# Sheet1.net
KiCad netlist of a schematic drawn in Altium Designer
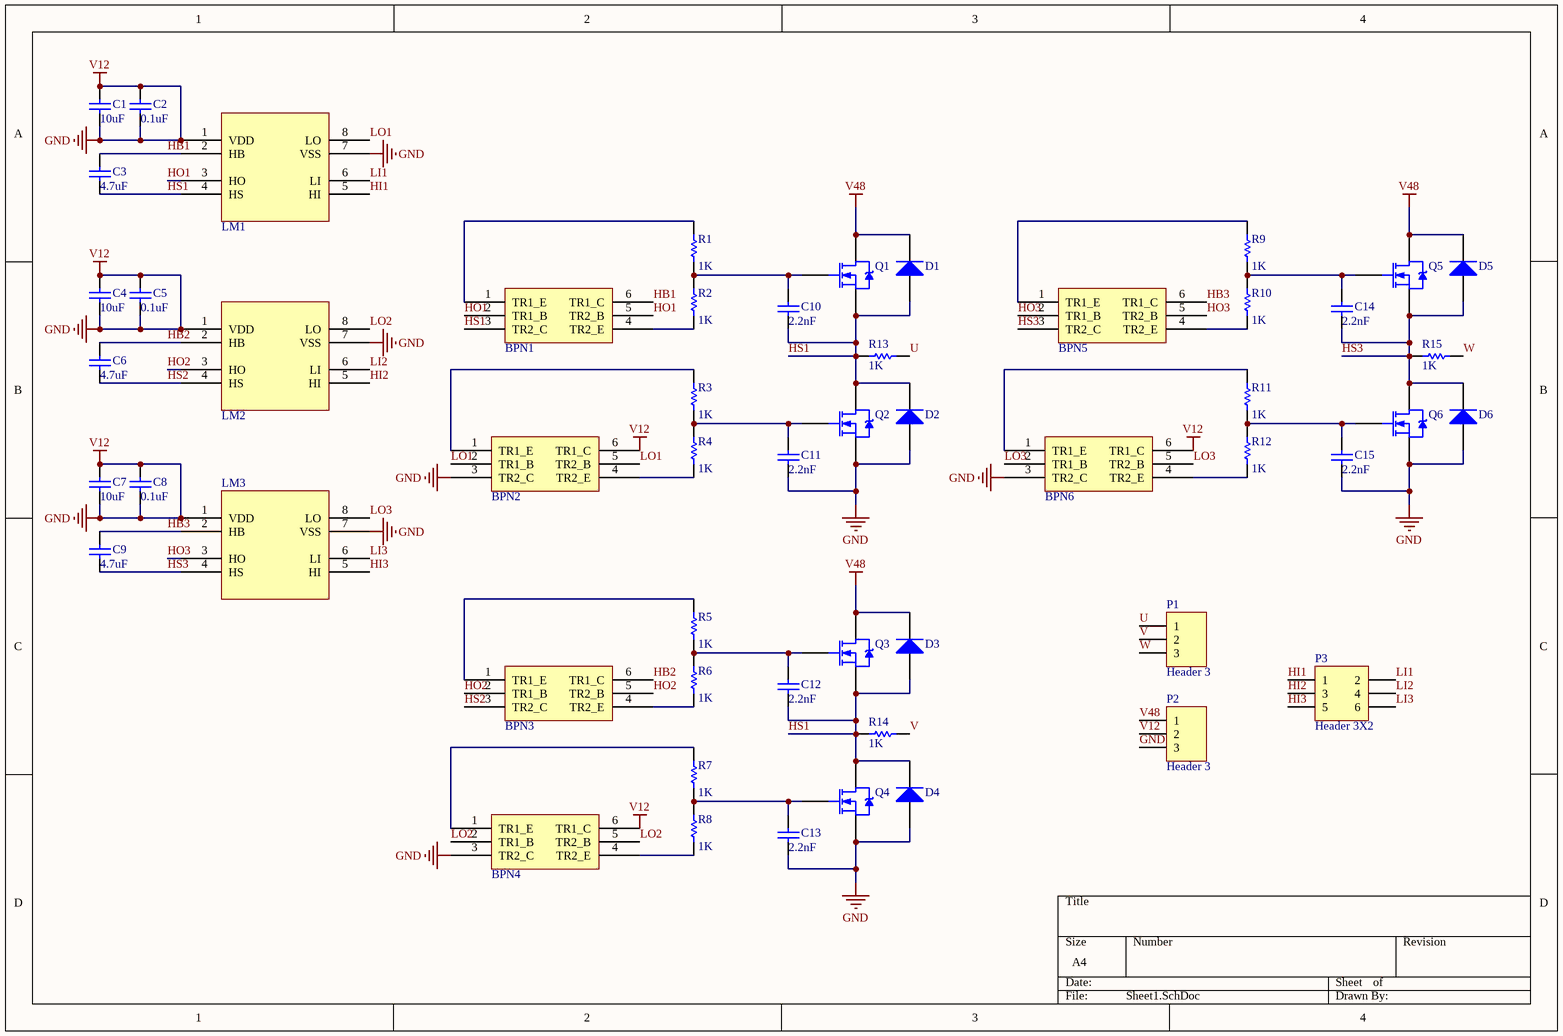
[diagram p0: Sheet1.SchDoc]

(export (version "E")
  (design (tool "Eeschema 10.0.6"))
  (components
    (comp (ref "BPN1") (value "BPN1") (footprint "BC847BPN") (libsource (lib "BC847BPN") (part "BC847BPN")))
    (comp (ref "BPN2") (value "BPN2") (footprint "BC847BPN") (libsource (lib "BC847BPN") (part "BC847BPN")))
    (comp (ref "BPN3") (value "BPN3") (footprint "BC847BPN") (libsource (lib "BC847BPN") (part "BC847BPN")))
    (comp (ref "BPN4") (value "BPN4") (footprint "BC847BPN") (libsource (lib "BC847BPN") (part "BC847BPN")))
    (comp (ref "BPN5") (value "BPN5") (footprint "BC847BPN") (libsource (lib "BC847BPN") (part "BC847BPN")))
    (comp (ref "BPN6") (value "BPN6") (footprint "BC847BPN") (libsource (lib "BC847BPN") (part "BC847BPN")))
    (comp (ref "C1")
      (value "10uF")
      (footprint "6-0805_M")
      (description "Capacitor")
      (fields (field (name "Comment") "Cap") (field (name "PUBLISHER") "Altium Limited"))
      (libsource (lib "Miscellaneous Devices") (part "Cap"))
    )
    (comp (ref "C2")
      (value "0.1uF")
      (footprint "6-0805_M")
      (description "Capacitor")
      (fields (field (name "Comment") "Cap") (field (name "PUBLISHER") "Altium Limited"))
      (libsource (lib "Miscellaneous Devices") (part "Cap"))
    )
    (comp (ref "C3")
      (value "4.7uF")
      (footprint "6-0805_M")
      (description "Capacitor")
      (fields (field (name "Comment") "Cap") (field (name "PUBLISHER") "Altium Limited"))
      (libsource (lib "Miscellaneous Devices") (part "Cap"))
    )
    (comp (ref "C4")
      (value "10uF")
      (footprint "6-0805_M")
      (description "Capacitor")
      (fields (field (name "Comment") "Cap") (field (name "PUBLISHER") "Altium Limited"))
      (libsource (lib "Miscellaneous Devices") (part "Cap"))
    )
    (comp (ref "C5")
      (value "0.1uF")
      (footprint "6-0805_M")
      (description "Capacitor")
      (fields (field (name "Comment") "Cap") (field (name "PUBLISHER") "Altium Limited"))
      (libsource (lib "Miscellaneous Devices") (part "Cap"))
    )
    (comp (ref "C6")
      (value "4.7uF")
      (footprint "6-0805_M")
      (description "Capacitor")
      (fields (field (name "Comment") "Cap") (field (name "PUBLISHER") "Altium Limited"))
      (libsource (lib "Miscellaneous Devices") (part "Cap"))
    )
    (comp (ref "C7")
      (value "10uF")
      (footprint "6-0805_M")
      (description "Capacitor")
      (fields (field (name "Comment") "Cap") (field (name "PUBLISHER") "Altium Limited"))
      (libsource (lib "Miscellaneous Devices") (part "Cap"))
    )
    (comp (ref "C8")
      (value "0.1uF")
      (footprint "6-0805_M")
      (description "Capacitor")
      (fields (field (name "Comment") "Cap") (field (name "PUBLISHER") "Altium Limited"))
      (libsource (lib "Miscellaneous Devices") (part "Cap"))
    )
    (comp (ref "C9")
      (value "4.7uF")
      (footprint "6-0805_M")
      (description "Capacitor")
      (fields (field (name "Comment") "Cap") (field (name "PUBLISHER") "Altium Limited"))
      (libsource (lib "Miscellaneous Devices") (part "Cap"))
    )
    (comp (ref "C10")
      (value "2.2nF")
      (footprint "6-0805_M")
      (description "Capacitor")
      (fields (field (name "Comment") "Cap") (field (name "PUBLISHER") "Altium Limited"))
      (libsource (lib "Miscellaneous Devices") (part "Cap"))
    )
    (comp (ref "C11")
      (value "2.2nF")
      (footprint "6-0805_M")
      (description "Capacitor")
      (fields (field (name "Comment") "Cap") (field (name "PUBLISHER") "Altium Limited"))
      (libsource (lib "Miscellaneous Devices") (part "Cap"))
    )
    (comp (ref "C12")
      (value "2.2nF")
      (footprint "6-0805_M")
      (description "Capacitor")
      (fields (field (name "Comment") "Cap") (field (name "PUBLISHER") "Altium Limited"))
      (libsource (lib "Miscellaneous Devices") (part "Cap"))
    )
    (comp (ref "C13")
      (value "2.2nF")
      (footprint "6-0805_M")
      (description "Capacitor")
      (fields (field (name "Comment") "Cap") (field (name "PUBLISHER") "Altium Limited"))
      (libsource (lib "Miscellaneous Devices") (part "Cap"))
    )
    (comp (ref "C14")
      (value "2.2nF")
      (footprint "6-0805_M")
      (description "Capacitor")
      (fields (field (name "Comment") "Cap") (field (name "PUBLISHER") "Altium Limited"))
      (libsource (lib "Miscellaneous Devices") (part "Cap"))
    )
    (comp (ref "C15")
      (value "2.2nF")
      (footprint "6-0805_M")
      (description "Capacitor")
      (fields (field (name "Comment") "Cap") (field (name "PUBLISHER") "Altium Limited"))
      (libsource (lib "Miscellaneous Devices") (part "Cap"))
    )
    (comp (ref "D1")
      (value "Diode 1N914")
      (footprint "12Z-2010")
      (description "High Conductance Fast Diode")
      (fields (field (name "PUBLISHER") "Altium Limited"))
      (libsource (lib "Miscellaneous Devices") (part "Diode 1N914"))
    )
    (comp (ref "D2")
      (value "Diode 1N914")
      (footprint "12Z-2010")
      (description "High Conductance Fast Diode")
      (fields (field (name "PUBLISHER") "Altium Limited"))
      (libsource (lib "Miscellaneous Devices") (part "Diode 1N914"))
    )
    (comp (ref "D3")
      (value "Diode 1N914")
      (footprint "12Z-2010")
      (description "High Conductance Fast Diode")
      (fields (field (name "PUBLISHER") "Altium Limited"))
      (libsource (lib "Miscellaneous Devices") (part "Diode 1N914"))
    )
    (comp (ref "D4")
      (value "Diode 1N914")
      (footprint "12Z-2010")
      (description "High Conductance Fast Diode")
      (fields (field (name "PUBLISHER") "Altium Limited"))
      (libsource (lib "Miscellaneous Devices") (part "Diode 1N914"))
    )
    (comp (ref "D5")
      (value "Diode 1N914")
      (footprint "12Z-2010")
      (description "High Conductance Fast Diode")
      (fields (field (name "PUBLISHER") "Altium Limited"))
      (libsource (lib "Miscellaneous Devices") (part "Diode 1N914"))
    )
    (comp (ref "D6")
      (value "Diode 1N914")
      (footprint "12Z-2010")
      (description "High Conductance Fast Diode")
      (fields (field (name "PUBLISHER") "Altium Limited"))
      (libsource (lib "Miscellaneous Devices") (part "Diode 1N914"))
    )
    (comp (ref "LM1") (value "LM1") (footprint "LM5101A") (libsource (lib "LM5101A") (part "LM5101A")))
    (comp (ref "LM2") (value "LM2") (footprint "LM5101A") (libsource (lib "LM5101A") (part "LM5101A")))
    (comp (ref "LM3") (value "LM3") (footprint "LM5101A") (libsource (lib "LM5101A") (part "LM5101A")))
    (comp (ref "P1")
      (value "Header 3")
      (footprint "HDR1X3")
      (description "Header, 3-Pin")
      (fields (field (name "PUBLISHER") "Altium Limited"))
      (libsource (lib "Miscellaneous Connectors") (part "Header 3"))
    )
    (comp (ref "P2")
      (value "Header 3")
      (footprint "HDR1X3")
      (description "Header, 3-Pin")
      (fields (field (name "PUBLISHER") "Altium Limited"))
      (libsource (lib "Miscellaneous Connectors") (part "Header 3"))
    )
    (comp (ref "P3")
      (value "Header 3X2")
      (footprint "HDR2X3")
      (description "Header, 3-Pin, Dual row")
      (fields (field (name "PUBLISHER") "Altium Limited"))
      (libsource (lib "Miscellaneous Connectors") (part "Header 3X2"))
    )
    (comp (ref "Q1")
      (value "NMOS-2")
      (footprint "SOT-23_M")
      (description "N-Channel Power MOSFET")
      (fields (field (name "PUBLISHER") "Altium Limited"))
      (libsource (lib "Miscellaneous Devices") (part "NMOS-2"))
    )
    (comp (ref "Q2")
      (value "NMOS-2")
      (footprint "SOT23_M")
      (description "N-Channel Power MOSFET")
      (fields (field (name "PUBLISHER") "Altium Limited"))
      (libsource (lib "Miscellaneous Devices") (part "NMOS-2"))
    )
    (comp (ref "Q3")
      (value "NMOS-2")
      (footprint "SOT-23_M")
      (description "N-Channel Power MOSFET")
      (fields (field (name "PUBLISHER") "Altium Limited"))
      (libsource (lib "Miscellaneous Devices") (part "NMOS-2"))
    )
    (comp (ref "Q4")
      (value "NMOS-2")
      (footprint "SOT23_M")
      (description "N-Channel Power MOSFET")
      (fields (field (name "PUBLISHER") "Altium Limited"))
      (libsource (lib "Miscellaneous Devices") (part "NMOS-2"))
    )
    (comp (ref "Q5")
      (value "NMOS-2")
      (footprint "SOT-23_M")
      (description "N-Channel Power MOSFET")
      (fields (field (name "PUBLISHER") "Altium Limited"))
      (libsource (lib "Miscellaneous Devices") (part "NMOS-2"))
    )
    (comp (ref "Q6")
      (value "NMOS-2")
      (footprint "SOT23_M")
      (description "N-Channel Power MOSFET")
      (fields (field (name "PUBLISHER") "Altium Limited"))
      (libsource (lib "Miscellaneous Devices") (part "NMOS-2"))
    )
    (comp (ref "R1")
      (value "1K")
      (footprint "6-0805_M")
      (description "Resistor")
      (fields (field (name "Comment") "Res1") (field (name "PUBLISHER") "Altium Limited"))
      (libsource (lib "Miscellaneous Devices") (part "Res1"))
    )
    (comp (ref "R2")
      (value "1K")
      (footprint "6-0805_M")
      (description "Resistor")
      (fields (field (name "Comment") "Res1") (field (name "PUBLISHER") "Altium Limited"))
      (libsource (lib "Miscellaneous Devices") (part "Res1"))
    )
    (comp (ref "R3")
      (value "1K")
      (footprint "6-0805_M")
      (description "Resistor")
      (fields (field (name "Comment") "Res1") (field (name "PUBLISHER") "Altium Limited"))
      (libsource (lib "Miscellaneous Devices") (part "Res1"))
    )
    (comp (ref "R4")
      (value "1K")
      (footprint "6-0805_M")
      (description "Resistor")
      (fields (field (name "Comment") "Res1") (field (name "PUBLISHER") "Altium Limited"))
      (libsource (lib "Miscellaneous Devices") (part "Res1"))
    )
    (comp (ref "R5")
      (value "1K")
      (footprint "6-0805_M")
      (description "Resistor")
      (fields (field (name "Comment") "Res1") (field (name "PUBLISHER") "Altium Limited"))
      (libsource (lib "Miscellaneous Devices") (part "Res1"))
    )
    (comp (ref "R6")
      (value "1K")
      (footprint "6-0805_M")
      (description "Resistor")
      (fields (field (name "Comment") "Res1") (field (name "PUBLISHER") "Altium Limited"))
      (libsource (lib "Miscellaneous Devices") (part "Res1"))
    )
    (comp (ref "R7")
      (value "1K")
      (footprint "6-0805_M")
      (description "Resistor")
      (fields (field (name "Comment") "Res1") (field (name "PUBLISHER") "Altium Limited"))
      (libsource (lib "Miscellaneous Devices") (part "Res1"))
    )
    (comp (ref "R8")
      (value "1K")
      (footprint "6-0805_M")
      (description "Resistor")
      (fields (field (name "Comment") "Res1") (field (name "PUBLISHER") "Altium Limited"))
      (libsource (lib "Miscellaneous Devices") (part "Res1"))
    )
    (comp (ref "R9")
      (value "1K")
      (footprint "6-0805_M")
      (description "Resistor")
      (fields (field (name "Comment") "Res1") (field (name "PUBLISHER") "Altium Limited"))
      (libsource (lib "Miscellaneous Devices") (part "Res1"))
    )
    (comp (ref "R10")
      (value "1K")
      (footprint "6-0805_M")
      (description "Resistor")
      (fields (field (name "Comment") "Res1") (field (name "PUBLISHER") "Altium Limited"))
      (libsource (lib "Miscellaneous Devices") (part "Res1"))
    )
    (comp (ref "R11")
      (value "1K")
      (footprint "6-0805_M")
      (description "Resistor")
      (fields (field (name "Comment") "Res1") (field (name "PUBLISHER") "Altium Limited"))
      (libsource (lib "Miscellaneous Devices") (part "Res1"))
    )
    (comp (ref "R12")
      (value "1K")
      (footprint "6-0805_M")
      (description "Resistor")
      (fields (field (name "Comment") "Res1") (field (name "PUBLISHER") "Altium Limited"))
      (libsource (lib "Miscellaneous Devices") (part "Res1"))
    )
    (comp (ref "R13")
      (value "1K")
      (footprint "6-0805_M")
      (description "Resistor")
      (fields (field (name "Comment") "Res1") (field (name "PUBLISHER") "Altium Limited"))
      (libsource (lib "Miscellaneous Devices") (part "Res1"))
    )
    (comp (ref "R14")
      (value "1K")
      (footprint "6-0805_M")
      (description "Resistor")
      (fields (field (name "Comment") "Res1") (field (name "PUBLISHER") "Altium Limited"))
      (libsource (lib "Miscellaneous Devices") (part "Res1"))
    )
    (comp (ref "R15")
      (value "1K")
      (footprint "6-0805_M")
      (description "Resistor")
      (fields (field (name "Comment") "Res1") (field (name "PUBLISHER") "Altium Limited"))
      (libsource (lib "Miscellaneous Devices") (part "Res1"))
    )
  )
  (nets
    (net (code "1") (name "/HB1") (class "Default")
      (node (ref "BPN1") (pin "6") (pinfunction "TR1_C_6") (pintype "passive"))
      (node (ref "C3") (pin "2") (pinfunction "2_2") (pintype "passive"))
      (node (ref "LM1") (pin "2") (pinfunction "HB_2") (pintype "passive"))
    )
    (net (code "2") (name "/HB2") (class "Default")
      (node (ref "BPN3") (pin "6") (pinfunction "TR1_C_6") (pintype "passive"))
      (node (ref "C6") (pin "2") (pinfunction "2_2") (pintype "passive"))
      (node (ref "LM2") (pin "2") (pinfunction "HB_2") (pintype "passive"))
    )
    (net (code "3") (name "/HB3") (class "Default")
      (node (ref "BPN5") (pin "6") (pinfunction "TR1_C_6") (pintype "passive"))
      (node (ref "C9") (pin "2") (pinfunction "2_2") (pintype "passive"))
      (node (ref "LM3") (pin "2") (pinfunction "HB_2") (pintype "passive"))
    )
    (net (code "4") (name "/HI1") (class "Default")
      (node (ref "LM1") (pin "5") (pinfunction "HI_5") (pintype "passive"))
      (node (ref "P3") (pin "1") (pinfunction "1_1") (pintype "passive"))
    )
    (net (code "5") (name "/HI2") (class "Default")
      (node (ref "LM2") (pin "5") (pinfunction "HI_5") (pintype "passive"))
      (node (ref "P3") (pin "3") (pinfunction "3_3") (pintype "passive"))
    )
    (net (code "6") (name "/HI3") (class "Default")
      (node (ref "LM3") (pin "5") (pinfunction "HI_5") (pintype "passive"))
      (node (ref "P3") (pin "5") (pinfunction "5_5") (pintype "passive"))
    )
    (net (code "7") (name "/HO1") (class "Default")
      (node (ref "BPN1") (pin "2") (pinfunction "TR1_B_2") (pintype "passive"))
      (node (ref "BPN1") (pin "5") (pinfunction "TR2_B_5") (pintype "passive"))
      (node (ref "LM1") (pin "3") (pinfunction "HO_3") (pintype "passive"))
    )
    (net (code "8") (name "/HO2") (class "Default")
      (node (ref "BPN3") (pin "2") (pinfunction "TR1_B_2") (pintype "passive"))
      (node (ref "BPN3") (pin "5") (pinfunction "TR2_B_5") (pintype "passive"))
      (node (ref "LM2") (pin "3") (pinfunction "HO_3") (pintype "passive"))
    )
    (net (code "9") (name "/HO3") (class "Default")
      (node (ref "BPN5") (pin "2") (pinfunction "TR1_B_2") (pintype "passive"))
      (node (ref "BPN5") (pin "5") (pinfunction "TR2_B_5") (pintype "passive"))
      (node (ref "LM3") (pin "3") (pinfunction "HO_3") (pintype "passive"))
    )
    (net (code "10") (name "/HS1") (class "Default")
      (node (ref "BPN1") (pin "3") (pinfunction "TR2_C_3") (pintype "passive"))
      (node (ref "C10") (pin "1") (pinfunction "1_1") (pintype "passive"))
      (node (ref "C12") (pin "1") (pinfunction "1_1") (pintype "passive"))
      (node (ref "C3") (pin "1") (pinfunction "1_1") (pintype "passive"))
      (node (ref "D1") (pin "1") (pinfunction "A_1") (pintype "passive"))
      (node (ref "D2") (pin "2") (pinfunction "K_2") (pintype "passive"))
      (node (ref "D3") (pin "1") (pinfunction "A_1") (pintype "passive"))
      (node (ref "D4") (pin "2") (pinfunction "K_2") (pintype "passive"))
      (node (ref "LM1") (pin "4") (pinfunction "HS_4") (pintype "passive"))
      (node (ref "Q1") (pin "3") (pinfunction "S_3") (pintype "passive"))
      (node (ref "Q2") (pin "2") (pinfunction "D_2") (pintype "passive"))
      (node (ref "Q3") (pin "3") (pinfunction "S_3") (pintype "passive"))
      (node (ref "Q4") (pin "2") (pinfunction "D_2") (pintype "passive"))
      (node (ref "R13") (pin "2") (pinfunction "2_2") (pintype "passive"))
      (node (ref "R14") (pin "2") (pinfunction "2_2") (pintype "passive"))
    )
    (net (code "11") (name "/HS2") (class "Default")
      (node (ref "BPN3") (pin "3") (pinfunction "TR2_C_3") (pintype "passive"))
      (node (ref "C6") (pin "1") (pinfunction "1_1") (pintype "passive"))
      (node (ref "LM2") (pin "4") (pinfunction "HS_4") (pintype "passive"))
    )
    (net (code "12") (name "/HS3") (class "Default")
      (node (ref "BPN5") (pin "3") (pinfunction "TR2_C_3") (pintype "passive"))
      (node (ref "C14") (pin "1") (pinfunction "1_1") (pintype "passive"))
      (node (ref "C9") (pin "1") (pinfunction "1_1") (pintype "passive"))
      (node (ref "D5") (pin "1") (pinfunction "A_1") (pintype "passive"))
      (node (ref "D6") (pin "2") (pinfunction "K_2") (pintype "passive"))
      (node (ref "LM3") (pin "4") (pinfunction "HS_4") (pintype "passive"))
      (node (ref "Q5") (pin "3") (pinfunction "S_3") (pintype "passive"))
      (node (ref "Q6") (pin "2") (pinfunction "D_2") (pintype "passive"))
      (node (ref "R15") (pin "2") (pinfunction "2_2") (pintype "passive"))
    )
    (net (code "13") (name "/LI1") (class "Default")
      (node (ref "LM1") (pin "6") (pinfunction "LI_6") (pintype "passive"))
      (node (ref "P3") (pin "2") (pinfunction "2_2") (pintype "passive"))
    )
    (net (code "14") (name "/LI2") (class "Default")
      (node (ref "LM2") (pin "6") (pinfunction "LI_6") (pintype "passive"))
      (node (ref "P3") (pin "4") (pinfunction "4_4") (pintype "passive"))
    )
    (net (code "15") (name "/LI3") (class "Default")
      (node (ref "LM3") (pin "6") (pinfunction "LI_6") (pintype "passive"))
      (node (ref "P3") (pin "6") (pinfunction "6_6") (pintype "passive"))
    )
    (net (code "16") (name "/LO1") (class "Default")
      (node (ref "BPN2") (pin "2") (pinfunction "TR1_B_2") (pintype "passive"))
      (node (ref "BPN2") (pin "5") (pinfunction "TR2_B_5") (pintype "passive"))
      (node (ref "LM1") (pin "8") (pinfunction "LO_8") (pintype "passive"))
    )
    (net (code "17") (name "/LO2") (class "Default")
      (node (ref "BPN4") (pin "2") (pinfunction "TR1_B_2") (pintype "passive"))
      (node (ref "BPN4") (pin "5") (pinfunction "TR2_B_5") (pintype "passive"))
      (node (ref "LM2") (pin "8") (pinfunction "LO_8") (pintype "passive"))
    )
    (net (code "18") (name "/LO3") (class "Default")
      (node (ref "BPN6") (pin "2") (pinfunction "TR1_B_2") (pintype "passive"))
      (node (ref "BPN6") (pin "5") (pinfunction "TR2_B_5") (pintype "passive"))
      (node (ref "LM3") (pin "8") (pinfunction "LO_8") (pintype "passive"))
    )
    (net (code "19") (name "/U") (class "Default")
      (node (ref "P1") (pin "1") (pinfunction "1_1") (pintype "passive"))
      (node (ref "R13") (pin "1") (pinfunction "1_1") (pintype "passive"))
    )
    (net (code "20") (name "/V") (class "Default")
      (node (ref "P1") (pin "2") (pinfunction "2_2") (pintype "passive"))
      (node (ref "R14") (pin "1") (pinfunction "1_1") (pintype "passive"))
    )
    (net (code "21") (name "/W") (class "Default")
      (node (ref "P1") (pin "3") (pinfunction "3_3") (pintype "passive"))
      (node (ref "R15") (pin "1") (pinfunction "1_1") (pintype "passive"))
    )
    (net (code "22") (name "GND") (class "Default")
      (node (ref "BPN2") (pin "3") (pinfunction "TR2_C_3") (pintype "passive"))
      (node (ref "BPN2") (pin "6") (pinfunction "TR1_C_6") (pintype "passive"))
      (node (ref "BPN4") (pin "3") (pinfunction "TR2_C_3") (pintype "passive"))
      (node (ref "BPN4") (pin "6") (pinfunction "TR1_C_6") (pintype "passive"))
      (node (ref "BPN6") (pin "3") (pinfunction "TR2_C_3") (pintype "passive"))
      (node (ref "BPN6") (pin "6") (pinfunction "TR1_C_6") (pintype "passive"))
      (node (ref "C1") (pin "1") (pinfunction "1_1") (pintype "passive"))
      (node (ref "C1") (pin "2") (pinfunction "2_2") (pintype "passive"))
      (node (ref "C11") (pin "1") (pinfunction "1_1") (pintype "passive"))
      (node (ref "C13") (pin "1") (pinfunction "1_1") (pintype "passive"))
      (node (ref "C15") (pin "1") (pinfunction "1_1") (pintype "passive"))
      (node (ref "C2") (pin "1") (pinfunction "1_1") (pintype "passive"))
      (node (ref "C2") (pin "2") (pinfunction "2_2") (pintype "passive"))
      (node (ref "C4") (pin "1") (pinfunction "1_1") (pintype "passive"))
      (node (ref "C4") (pin "2") (pinfunction "2_2") (pintype "passive"))
      (node (ref "C5") (pin "1") (pinfunction "1_1") (pintype "passive"))
      (node (ref "C5") (pin "2") (pinfunction "2_2") (pintype "passive"))
      (node (ref "C7") (pin "1") (pinfunction "1_1") (pintype "passive"))
      (node (ref "C7") (pin "2") (pinfunction "2_2") (pintype "passive"))
      (node (ref "C8") (pin "1") (pinfunction "1_1") (pintype "passive"))
      (node (ref "C8") (pin "2") (pinfunction "2_2") (pintype "passive"))
      (node (ref "D2") (pin "1") (pinfunction "A_1") (pintype "passive"))
      (node (ref "D4") (pin "1") (pinfunction "A_1") (pintype "passive"))
      (node (ref "D6") (pin "1") (pinfunction "A_1") (pintype "passive"))
      (node (ref "LM1") (pin "1") (pinfunction "VDD_1") (pintype "passive"))
      (node (ref "LM1") (pin "7") (pinfunction "VSS_7") (pintype "passive"))
      (node (ref "LM2") (pin "1") (pinfunction "VDD_1") (pintype "passive"))
      (node (ref "LM2") (pin "7") (pinfunction "VSS_7") (pintype "passive"))
      (node (ref "LM3") (pin "1") (pinfunction "VDD_1") (pintype "passive"))
      (node (ref "LM3") (pin "7") (pinfunction "VSS_7") (pintype "passive"))
      (node (ref "P2") (pin "2") (pinfunction "2_2") (pintype "passive"))
      (node (ref "P2") (pin "3") (pinfunction "3_3") (pintype "passive"))
      (node (ref "Q2") (pin "3") (pinfunction "S_3") (pintype "passive"))
      (node (ref "Q4") (pin "3") (pinfunction "S_3") (pintype "passive"))
      (node (ref "Q6") (pin "3") (pinfunction "S_3") (pintype "passive"))
    )
    (net (code "23") (name "Net-(BPN1-TR1_E)") (class "Default")
      (node (ref "BPN1") (pin "1") (pinfunction "TR1_E_1") (pintype "passive"))
      (node (ref "R1") (pin "2") (pinfunction "2_2") (pintype "passive"))
    )
    (net (code "24") (name "Net-(BPN1-TR2_E)") (class "Default")
      (node (ref "BPN1") (pin "4") (pinfunction "TR2_E_4") (pintype "passive"))
      (node (ref "R2") (pin "1") (pinfunction "1_1") (pintype "passive"))
    )
    (net (code "25") (name "Net-(BPN2-TR1_E)") (class "Default")
      (node (ref "BPN2") (pin "1") (pinfunction "TR1_E_1") (pintype "passive"))
      (node (ref "R3") (pin "2") (pinfunction "2_2") (pintype "passive"))
    )
    (net (code "26") (name "Net-(BPN2-TR2_E)") (class "Default")
      (node (ref "BPN2") (pin "4") (pinfunction "TR2_E_4") (pintype "passive"))
      (node (ref "R4") (pin "1") (pinfunction "1_1") (pintype "passive"))
    )
    (net (code "27") (name "Net-(BPN3-TR1_E)") (class "Default")
      (node (ref "BPN3") (pin "1") (pinfunction "TR1_E_1") (pintype "passive"))
      (node (ref "R5") (pin "2") (pinfunction "2_2") (pintype "passive"))
    )
    (net (code "28") (name "Net-(BPN3-TR2_E)") (class "Default")
      (node (ref "BPN3") (pin "4") (pinfunction "TR2_E_4") (pintype "passive"))
      (node (ref "R6") (pin "1") (pinfunction "1_1") (pintype "passive"))
    )
    (net (code "29") (name "Net-(BPN4-TR1_E)") (class "Default")
      (node (ref "BPN4") (pin "1") (pinfunction "TR1_E_1") (pintype "passive"))
      (node (ref "R7") (pin "2") (pinfunction "2_2") (pintype "passive"))
    )
    (net (code "30") (name "Net-(BPN4-TR2_E)") (class "Default")
      (node (ref "BPN4") (pin "4") (pinfunction "TR2_E_4") (pintype "passive"))
      (node (ref "R8") (pin "1") (pinfunction "1_1") (pintype "passive"))
    )
    (net (code "31") (name "Net-(BPN5-TR1_E)") (class "Default")
      (node (ref "BPN5") (pin "1") (pinfunction "TR1_E_1") (pintype "passive"))
      (node (ref "R9") (pin "2") (pinfunction "2_2") (pintype "passive"))
    )
    (net (code "32") (name "Net-(BPN5-TR2_E)") (class "Default")
      (node (ref "BPN5") (pin "4") (pinfunction "TR2_E_4") (pintype "passive"))
      (node (ref "R10") (pin "1") (pinfunction "1_1") (pintype "passive"))
    )
    (net (code "33") (name "Net-(BPN6-TR1_E)") (class "Default")
      (node (ref "BPN6") (pin "1") (pinfunction "TR1_E_1") (pintype "passive"))
      (node (ref "R11") (pin "2") (pinfunction "2_2") (pintype "passive"))
    )
    (net (code "34") (name "Net-(BPN6-TR2_E)") (class "Default")
      (node (ref "BPN6") (pin "4") (pinfunction "TR2_E_4") (pintype "passive"))
      (node (ref "R12") (pin "1") (pinfunction "1_1") (pintype "passive"))
    )
    (net (code "35") (name "Net-(Q1-G)") (class "Default")
      (node (ref "C10") (pin "2") (pinfunction "2_2") (pintype "passive"))
      (node (ref "Q1") (pin "1") (pinfunction "G_1") (pintype "passive"))
      (node (ref "R1") (pin "1") (pinfunction "1_1") (pintype "passive"))
      (node (ref "R2") (pin "2") (pinfunction "2_2") (pintype "passive"))
    )
    (net (code "36") (name "Net-(Q2-G)") (class "Default")
      (node (ref "C11") (pin "2") (pinfunction "2_2") (pintype "passive"))
      (node (ref "Q2") (pin "1") (pinfunction "G_1") (pintype "passive"))
      (node (ref "R3") (pin "1") (pinfunction "1_1") (pintype "passive"))
      (node (ref "R4") (pin "2") (pinfunction "2_2") (pintype "passive"))
    )
    (net (code "37") (name "Net-(Q3-G)") (class "Default")
      (node (ref "C12") (pin "2") (pinfunction "2_2") (pintype "passive"))
      (node (ref "Q3") (pin "1") (pinfunction "G_1") (pintype "passive"))
      (node (ref "R5") (pin "1") (pinfunction "1_1") (pintype "passive"))
      (node (ref "R6") (pin "2") (pinfunction "2_2") (pintype "passive"))
    )
    (net (code "38") (name "Net-(Q4-G)") (class "Default")
      (node (ref "C13") (pin "2") (pinfunction "2_2") (pintype "passive"))
      (node (ref "Q4") (pin "1") (pinfunction "G_1") (pintype "passive"))
      (node (ref "R7") (pin "1") (pinfunction "1_1") (pintype "passive"))
      (node (ref "R8") (pin "2") (pinfunction "2_2") (pintype "passive"))
    )
    (net (code "39") (name "Net-(Q5-G)") (class "Default")
      (node (ref "C14") (pin "2") (pinfunction "2_2") (pintype "passive"))
      (node (ref "Q5") (pin "1") (pinfunction "G_1") (pintype "passive"))
      (node (ref "R10") (pin "2") (pinfunction "2_2") (pintype "passive"))
      (node (ref "R9") (pin "1") (pinfunction "1_1") (pintype "passive"))
    )
    (net (code "40") (name "Net-(Q6-G)") (class "Default")
      (node (ref "C15") (pin "2") (pinfunction "2_2") (pintype "passive"))
      (node (ref "Q6") (pin "1") (pinfunction "G_1") (pintype "passive"))
      (node (ref "R11") (pin "1") (pinfunction "1_1") (pintype "passive"))
      (node (ref "R12") (pin "2") (pinfunction "2_2") (pintype "passive"))
    )
    (net (code "41") (name "V48") (class "Default")
      (node (ref "D1") (pin "2") (pinfunction "K_2") (pintype "passive"))
      (node (ref "D3") (pin "2") (pinfunction "K_2") (pintype "passive"))
      (node (ref "D5") (pin "2") (pinfunction "K_2") (pintype "passive"))
      (node (ref "P2") (pin "1") (pinfunction "1_1") (pintype "passive"))
      (node (ref "Q1") (pin "2") (pinfunction "D_2") (pintype "passive"))
      (node (ref "Q3") (pin "2") (pinfunction "D_2") (pintype "passive"))
      (node (ref "Q5") (pin "2") (pinfunction "D_2") (pintype "passive"))
    )
  )
)
